# 6_Current_Sensing.net
KiCad netlist of a schematic drawn in Altium Designer
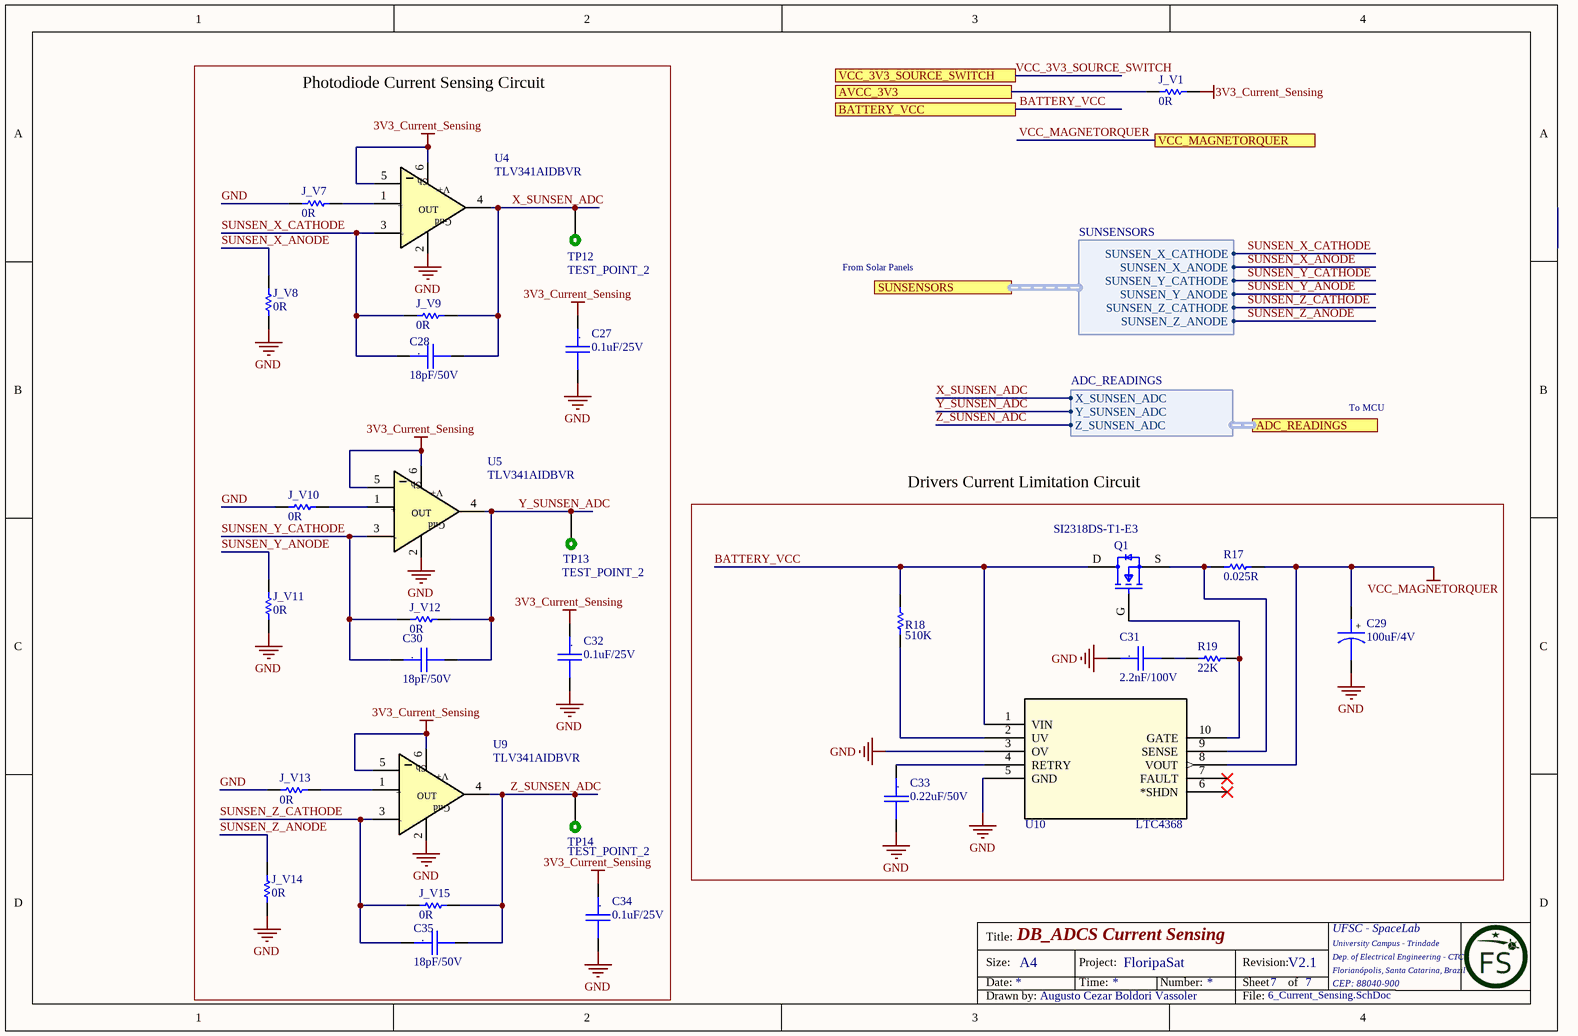
[diagram p0: 6_Current_Sensing.SchDoc]

(export (version "E")
  (design (tool "Eeschema 10.0.6"))
  (components
    (comp (ref "C27")
      (value "0.1uF/25V")
      (footprint "CC0805")
      (description "CAP CER 0.1UF 25V 10% X7R 0805")
      (fields (field (name "PARTNUMBER") "CC0805KRX7R8BB104"))
      (libsource (lib "PCB_Eng_Model_OBDH_2") (part "Cap_Cer_X7R_0.1uF_25V_0805"))
    )
    (comp (ref "C28")
      (value "18pF/50V")
      (footprint "CC0805")
      (description "CAP CER 18pF 50V 5% X7R 0805")
      (fields (field (name "PARTNUMBER") "CC0805JRNPO9BN180"))
      (libsource (lib "PCB_Eng_Model_OBDH_2") (part "Cap_Cer_X7R_18pF_50V_0805"))
    )
    (comp (ref "C29")
      (value "100uF/4V")
      (footprint "CC0805_Tantalum")
      (description "CAP TANT 100UF 4V 20% 0805")
      (fields
        (field (name "MANUFACTURER") "Kyocera AVX")
        (field (name "MANUFACTURER PART NUMBER") "TACR107M004RTA")
      )
      (libsource (lib "PCB_Eng_Model_OBDH_2") (part "Cap_Tant_SMD_100uF_4V_0805"))
    )
    (comp (ref "C30")
      (value "18pF/50V")
      (footprint "CC0805")
      (description "CAP CER 18pF 50V 5% X7R 0805")
      (fields (field (name "PARTNUMBER") "CC0805JRNPO9BN180"))
      (libsource (lib "PCB_Eng_Model_OBDH_2") (part "Cap_Cer_X7R_18pF_50V_0805"))
    )
    (comp (ref "C31")
      (value "2.2nF/100V")
      (footprint "CC0805")
      (description "Cap Cer 0.0022uF 100V X7R 5% 0805")
      (fields
        (field (name "MANUFACTURER") "Kyocera AVX")
        (field (name "MANUFACTURER PART NUMBER") "08051C222JAT2A")
      )
      (libsource (lib "PCB_Eng_Model_OBDH_2") (part "Cap_Cer_X7R_0.0022uF_0805"))
    )
    (comp (ref "C32")
      (value "0.1uF/25V")
      (footprint "CC0805")
      (description "CAP CER 0.1UF 25V 10% X7R 0805")
      (fields (field (name "PARTNUMBER") "CC0805KRX7R8BB104"))
      (libsource (lib "PCB_Eng_Model_OBDH_2") (part "Cap_Cer_X7R_0.1uF_25V_0805"))
    )
    (comp (ref "C33")
      (value "0.22uF/50V")
      (footprint "CC0805")
      (description "CAP CER 0.22UF 50V X7R 0805")
      (fields
        (field (name "MANUFACTURER") "KEMET")
        (field (name "MANUFACTURER PART NUMBER") "C0805C224K5RACTU")
      )
      (libsource (lib "PCB_Eng_Model_OBDH_2") (part "Cap_Cer_X7R_0.22uF_0805"))
    )
    (comp (ref "C34")
      (value "0.1uF/25V")
      (footprint "CC0805")
      (description "CAP CER 0.1UF 25V 10% X7R 0805")
      (fields (field (name "PARTNUMBER") "CC0805KRX7R8BB104"))
      (libsource (lib "PCB_Eng_Model_OBDH_2") (part "Cap_Cer_X7R_0.1uF_25V_0805"))
    )
    (comp (ref "C35")
      (value "18pF/50V")
      (footprint "CC0805")
      (description "CAP CER 18pF 50V 5% X7R 0805")
      (fields (field (name "PARTNUMBER") "CC0805JRNPO9BN180"))
      (libsource (lib "PCB_Eng_Model_OBDH_2") (part "Cap_Cer_X7R_18pF_50V_0805"))
    )
    (comp (ref "J_V1")
      (value "0R")
      (footprint "PCB_OBDH:0805")
      (description "RES 0R OHM 1/16W JUMPER 0805")
      (fields (field (name "PARTNUMBER") "CRCW08050000Z0EA"))
      (libsource (lib "PCB_DB_ADCS") (part "R0R_JUMPER_1/16W_0805"))
    )
    (comp (ref "J_V7")
      (value "0R")
      (footprint "0805-LED")
      (description "RES 0R OHM 1/16W JUMPER 0805")
      (fields (field (name "PARTNUMBER") "CRCW08050000Z0EA"))
      (libsource (lib "PCB_Eng_Model_OBDH_2") (part "R0R_JUMPER_1/16W_0805"))
    )
    (comp (ref "J_V8")
      (value "0R")
      (footprint "0805-LED")
      (description "RES 0R OHM 1/16W JUMPER 0805")
      (fields (field (name "PARTNUMBER") "CRCW08050000Z0EA"))
      (libsource (lib "PCB_Eng_Model_OBDH_2") (part "R0R_JUMPER_1/16W_0805"))
    )
    (comp (ref "J_V9")
      (value "0R")
      (footprint "0805-LED")
      (description "RES 0R OHM 1/16W JUMPER 0805")
      (fields (field (name "PARTNUMBER") "CRCW08050000Z0EA"))
      (libsource (lib "PCB_Eng_Model_OBDH_2") (part "R0R_JUMPER_1/16W_0805"))
    )
    (comp (ref "J_V10")
      (value "0R")
      (footprint "0805-LED")
      (description "RES 0R OHM 1/16W JUMPER 0805")
      (fields (field (name "PARTNUMBER") "CRCW08050000Z0EA"))
      (libsource (lib "PCB_Eng_Model_OBDH_2") (part "R0R_JUMPER_1/16W_0805"))
    )
    (comp (ref "J_V11")
      (value "0R")
      (footprint "0805-LED")
      (description "RES 0R OHM 1/16W JUMPER 0805")
      (fields (field (name "PARTNUMBER") "CRCW08050000Z0EA"))
      (libsource (lib "PCB_Eng_Model_OBDH_2") (part "R0R_JUMPER_1/16W_0805"))
    )
    (comp (ref "J_V12")
      (value "0R")
      (footprint "0805-LED")
      (description "RES 0R OHM 1/16W JUMPER 0805")
      (fields (field (name "PARTNUMBER") "CRCW08050000Z0EA"))
      (libsource (lib "PCB_Eng_Model_OBDH_2") (part "R0R_JUMPER_1/16W_0805"))
    )
    (comp (ref "J_V13")
      (value "0R")
      (footprint "0805-LED")
      (description "RES 0R OHM 1/16W JUMPER 0805")
      (fields (field (name "PARTNUMBER") "CRCW08050000Z0EA"))
      (libsource (lib "PCB_Eng_Model_OBDH_2") (part "R0R_JUMPER_1/16W_0805"))
    )
    (comp (ref "J_V14")
      (value "0R")
      (footprint "0805-LED")
      (description "RES 0R OHM 1/16W JUMPER 0805")
      (fields (field (name "PARTNUMBER") "CRCW08050000Z0EA"))
      (libsource (lib "PCB_Eng_Model_OBDH_2") (part "R0R_JUMPER_1/16W_0805"))
    )
    (comp (ref "J_V15")
      (value "0R")
      (footprint "0805-LED")
      (description "RES 0R OHM 1/16W JUMPER 0805")
      (fields (field (name "PARTNUMBER") "CRCW08050000Z0EA"))
      (libsource (lib "PCB_Eng_Model_OBDH_2") (part "R0R_JUMPER_1/16W_0805"))
    )
    (comp (ref "Q1")
      (value "SI2318DS-T1-E3")
      (footprint "FP-S-03946-MFG")
      (description "MOSFET N-CH 40V 3A SOT23-3")
      (fields
        (field (name "MANUFACTURER") "Vishay")
        (field (name "OCTOPART") "https://octopart.com/si2318ds-t1-e3-vishay-40866469")
      )
      (libsource (lib "PCB_DB_ADCS") (part "CMP-02550-000015-1"))
    )
    (comp (ref "R17")
      (value "0.025R")
      (footprint "1206")
      (description "RES 0.025 OHM - 0.25W 1% 1206")
      (fields
        (field (name "MANUFACTURER") "Vishay Dale")
        (field (name "MANUFACTURER PART NUMBER") "WSL1206R0250FBA")
      )
      (libsource (lib "PCB_Eng_Model_OBDH_2") (part "R0.025_1%_1/4W_1206"))
    )
    (comp (ref "R18")
      (value "510K")
      (footprint "0805")
      (description "RES 510K OHM 1/8W 1% 0805")
      (fields
        (field (name "MANUFACTURER") "Vishay")
        (field (name "MANUFACTURER PART NUMBER") "CRCW0805510KFKEA")
      )
      (libsource (lib "PCB_Eng_Model_OBDH_2") (part "R510K_1%_1/8W_0805"))
    )
    (comp (ref "R19")
      (value "22K")
      (footprint "0805-LED")
      (description "RES 22K OHM 1.25W 1% 0805")
      (fields
        (field (name "MANUFACTURER") "Vishay")
        (field (name "MANUFACTURER PART NUMBER") "CRCW080522K0FKEA")
      )
      (libsource (lib "PCB_Eng_Model_OBDH_2") (part "R22K_1%_1.25W_0805"))
    )
    (comp (ref "TP12")
      (value "TEST_POINT_2")
      (footprint "TEST_POINT_2")
      (description "Test point")
      (libsource (lib "PCB_Eng_Model_OBDH_2") (part "TEST_POINT_2"))
    )
    (comp (ref "TP13")
      (value "TEST_POINT_2")
      (footprint "TEST_POINT_2")
      (description "Test point")
      (libsource (lib "PCB_Eng_Model_OBDH_2") (part "TEST_POINT_2"))
    )
    (comp (ref "TP14")
      (value "TEST_POINT_2")
      (footprint "TEST_POINT_2")
      (description "Test point")
      (libsource (lib "PCB_Eng_Model_OBDH_2") (part "TEST_POINT_2"))
    )
    (comp (ref "U4")
      (value "TLV341AIDBVR")
      (footprint "SOT-23 6L")
      (libsource (lib "") (part "TLV341AIDBVR_1"))
    )
    (comp (ref "U5")
      (value "TLV341AIDBVR")
      (footprint "SOT-23 6L")
      (libsource (lib "") (part "TLV341AIDBVR_1"))
    )
    (comp (ref "U9")
      (value "TLV341AIDBVR")
      (footprint "SOT-23 6L")
      (libsource (lib "PCB_Eng_Model_OBDH_2") (part "TLV341AIDBVR"))
    )
    (comp (ref "U10")
      (value "LTC4368")
      (footprint "MSOP-10_MS")
      (description "LTC4368 - 100V UV/OV and Reverse Protection Controller with Bidirectional Circuit Breaker")
      (fields
        (field (name "MANUFACTURER") "Analog Devices")
        (field (name "MANUFACTURER PART NUMBER") "LTC4368IMS-2#PBF")
      )
      (libsource (lib "PCB_Eng_Model_OBDH_2") (part "LTC4368"))
    )
  )
  (nets
    (net (code "3") (name "/AVCC_3V3") (class "Default")
      (node (ref "J_V1") (pin "2") (pinfunction "2_2") (pintype "passive"))
    )
    (net (code "4") (name "/BATTERY_VCC") (class "Default")
      (node (ref "Q1") (pin "D") (pinfunction "D_D") (pintype "passive"))
      (node (ref "R18") (pin "1") (pinfunction "1_1") (pintype "passive"))
      (node (ref "U10") (pin "1") (pinfunction "VIN_1") (pintype "passive"))
    )
    (net (code "5") (name "/SUNSEN_X_ANODE") (class "Default")
      (node (ref "J_V8") (pin "2") (pinfunction "2_2") (pintype "passive"))
    )
    (net (code "6") (name "/SUNSEN_X_CATHODE") (class "Default")
      (node (ref "C28") (pin "1") (pinfunction "1_1") (pintype "passive"))
      (node (ref "J_V9") (pin "2") (pinfunction "2_2") (pintype "passive"))
      (node (ref "U4") (pin "3") (pinfunction "-IN_3") (pintype "passive"))
    )
    (net (code "7") (name "/SUNSEN_Y_ANODE") (class "Default")
      (node (ref "J_V11") (pin "1") (pinfunction "1_1") (pintype "passive"))
    )
    (net (code "8") (name "/SUNSEN_Y_CATHODE") (class "Default")
      (node (ref "C30") (pin "1") (pinfunction "1_1") (pintype "passive"))
      (node (ref "J_V12") (pin "2") (pinfunction "2_2") (pintype "passive"))
      (node (ref "U5") (pin "3") (pinfunction "-IN_3") (pintype "passive"))
    )
    (net (code "9") (name "/SUNSEN_Z_ANODE") (class "Default")
      (node (ref "J_V14") (pin "1") (pinfunction "1_1") (pintype "passive"))
    )
    (net (code "10") (name "/SUNSEN_Z_CATHODE") (class "Default")
      (node (ref "C35") (pin "1") (pinfunction "1_1") (pintype "passive"))
      (node (ref "J_V15") (pin "2") (pinfunction "2_2") (pintype "passive"))
      (node (ref "U9") (pin "3") (pinfunction "-IN_3") (pintype "passive"))
    )
    (net (code "12") (name "/X_SUNSEN_ADC") (class "Default")
      (node (ref "C28") (pin "2") (pinfunction "2_2") (pintype "passive"))
      (node (ref "J_V9") (pin "1") (pinfunction "1_1") (pintype "passive"))
      (node (ref "TP12") (pin "1") (pinfunction "1_1") (pintype "passive"))
      (node (ref "U4") (pin "4") (pinfunction "OUT_4") (pintype "passive"))
    )
    (net (code "13") (name "/Y_SUNSEN_ADC") (class "Default")
      (node (ref "C30") (pin "2") (pinfunction "2_2") (pintype "passive"))
      (node (ref "J_V12") (pin "1") (pinfunction "1_1") (pintype "passive"))
      (node (ref "TP13") (pin "1") (pinfunction "1_1") (pintype "passive"))
      (node (ref "U5") (pin "4") (pinfunction "OUT_4") (pintype "passive"))
    )
    (net (code "14") (name "/Z_SUNSEN_ADC") (class "Default")
      (node (ref "C35") (pin "2") (pinfunction "2_2") (pintype "passive"))
      (node (ref "J_V15") (pin "1") (pinfunction "1_1") (pintype "passive"))
      (node (ref "TP14") (pin "1") (pinfunction "1_1") (pintype "passive"))
      (node (ref "U9") (pin "4") (pinfunction "OUT_4") (pintype "passive"))
    )
    (net (code "17") (name "3V3_Current_Sensing") (class "Default")
      (node (ref "C27") (pin "1") (pinfunction "1_1") (pintype "passive"))
      (node (ref "C32") (pin "1") (pinfunction "1_1") (pintype "passive"))
      (node (ref "C34") (pin "1") (pinfunction "1_1") (pintype "passive"))
      (node (ref "J_V1") (pin "1") (pinfunction "1_1") (pintype "passive"))
      (node (ref "U4") (pin "5") (pinfunction "EN_5") (pintype "passive"))
      (node (ref "U4") (pin "6") (pinfunction "V+_6") (pintype "passive"))
      (node (ref "U5") (pin "5") (pinfunction "EN_5") (pintype "passive"))
      (node (ref "U5") (pin "6") (pinfunction "V+_6") (pintype "passive"))
      (node (ref "U9") (pin "5") (pinfunction "EN_5") (pintype "passive"))
      (node (ref "U9") (pin "6") (pinfunction "V+_6") (pintype "passive"))
    )
    (net (code "18") (name "GND") (class "Default")
      (node (ref "C27") (pin "2") (pinfunction "2_2") (pintype "passive"))
      (node (ref "C29") (pin "2") (pinfunction "2_2") (pintype "passive"))
      (node (ref "C31") (pin "1") (pinfunction "1_1") (pintype "passive"))
      (node (ref "C32") (pin "2") (pinfunction "2_2") (pintype "passive"))
      (node (ref "C33") (pin "2") (pinfunction "2_2") (pintype "passive"))
      (node (ref "C34") (pin "2") (pinfunction "2_2") (pintype "passive"))
      (node (ref "J_V10") (pin "2") (pinfunction "2_2") (pintype "passive"))
      (node (ref "J_V11") (pin "2") (pinfunction "2_2") (pintype "passive"))
      (node (ref "J_V13") (pin "2") (pinfunction "2_2") (pintype "passive"))
      (node (ref "J_V14") (pin "2") (pinfunction "2_2") (pintype "passive"))
      (node (ref "J_V7") (pin "2") (pinfunction "2_2") (pintype "passive"))
      (node (ref "J_V8") (pin "1") (pinfunction "1_1") (pintype "passive"))
      (node (ref "U10") (pin "3") (pinfunction "OV_3") (pintype "passive"))
      (node (ref "U10") (pin "5") (pinfunction "GND_5") (pintype "passive"))
      (node (ref "U4") (pin "2") (pinfunction "Gnd_2") (pintype "passive"))
      (node (ref "U5") (pin "2") (pinfunction "Gnd_2") (pintype "passive"))
      (node (ref "U9") (pin "2") (pinfunction "Gnd_2") (pintype "passive"))
    )
    (net (code "19") (name "Net-(C31-Pad2)") (class "Default")
      (node (ref "C31") (pin "2") (pinfunction "2_2") (pintype "passive"))
      (node (ref "R19") (pin "2") (pinfunction "2_2") (pintype "passive"))
    )
    (net (code "20") (name "Net-(U4-+IN)") (class "Default")
      (node (ref "J_V7") (pin "1") (pinfunction "1_1") (pintype "passive"))
      (node (ref "U4") (pin "1") (pinfunction "+IN_1") (pintype "passive"))
    )
    (net (code "21") (name "Net-(U5-+IN)") (class "Default")
      (node (ref "J_V10") (pin "1") (pinfunction "1_1") (pintype "passive"))
      (node (ref "U5") (pin "1") (pinfunction "+IN_1") (pintype "passive"))
    )
    (net (code "22") (name "Net-(U9-+IN)") (class "Default")
      (node (ref "J_V13") (pin "1") (pinfunction "1_1") (pintype "passive"))
      (node (ref "U9") (pin "1") (pinfunction "+IN_1") (pintype "passive"))
    )
    (net (code "23") (name "Net-(U10-GATE)") (class "Default")
      (node (ref "Q1") (pin "G") (pinfunction "G_G") (pintype "passive"))
      (node (ref "R19") (pin "1") (pinfunction "1_1") (pintype "passive"))
      (node (ref "U10") (pin "10") (pinfunction "GATE_10") (pintype "passive"))
    )
    (net (code "24") (name "Net-(U10-RETRY)") (class "Default")
      (node (ref "C33") (pin "1") (pinfunction "1_1") (pintype "passive"))
      (node (ref "U10") (pin "4") (pinfunction "RETRY_4") (pintype "passive"))
    )
    (net (code "25") (name "Net-(U10-SENSE)") (class "Default")
      (node (ref "Q1") (pin "S") (pinfunction "S_S") (pintype "passive"))
      (node (ref "R17") (pin "2") (pinfunction "2_2") (pintype "passive"))
      (node (ref "U10") (pin "9") (pinfunction "SENSE_9") (pintype "passive"))
    )
    (net (code "26") (name "Net-(U10-UV)") (class "Default")
      (node (ref "R18") (pin "2") (pinfunction "2_2") (pintype "passive"))
      (node (ref "U10") (pin "2") (pinfunction "UV_2") (pintype "passive"))
    )
    (net (code "27") (name "VCC_MAGNETORQUER") (class "Default")
      (node (ref "C29") (pin "1") (pinfunction "1_1") (pintype "passive"))
      (node (ref "R17") (pin "1") (pinfunction "1_1") (pintype "passive"))
      (node (ref "U10") (pin "8") (pinfunction "VOUT_8") (pintype "output"))
    )
    (net (code "28") (name "unconnected-(U10-*SHDN-Pad6)") (class "Default")
      (node (ref "U10") (pin "6") (pinfunction "*SHDN_6") (pintype "passive+no_connect"))
    )
    (net (code "29") (name "unconnected-(U10-FAULT-Pad7)") (class "Default")
      (node (ref "U10") (pin "7") (pinfunction "FAULT_7") (pintype "passive+no_connect"))
    )
  )
)
